# 04_Fan_Control.net
KiCad netlist of a schematic drawn in Altium Designer
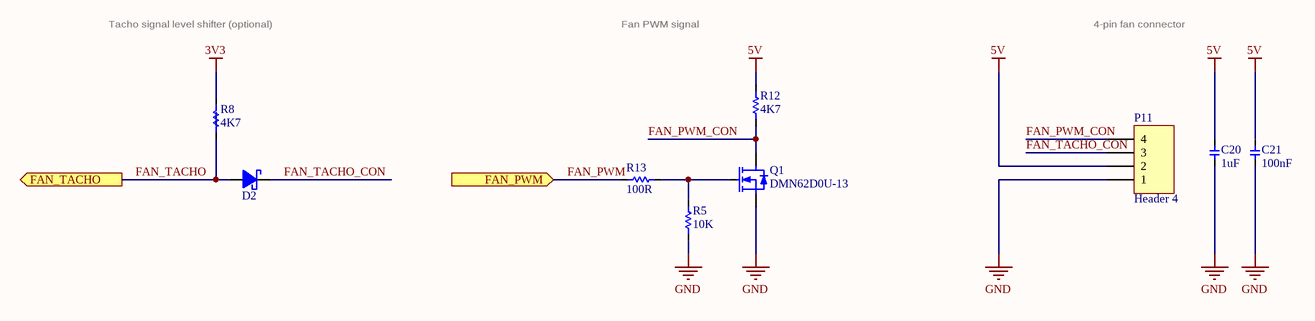
[diagram p0: 04_Fan_Control.SchDoc]

(export (version "E")
  (design (tool "Eeschema 10.0.6"))
  (components
    (comp (ref "C20")
      (value "1uF")
      (footprint "Moji Footprintovi:0603 - CAP HS")
      (description "Capacitor")
      (fields
        (field (name "MANUFACTURER") "Samsung Electro-Mechanics")
        (field (name "MANUFACTURER PART NUMBER") "CL10A105KB8NNNC")
      )
      (libsource (lib "Moji Schematici (1)") (part "Cap"))
    )
    (comp (ref "C21")
      (value "100nF")
      (footprint "Moji Footprintovi:0603 - CAP HS")
      (description "Capacitor")
      (fields
        (field (name "MANUFACTURER") "Samsung Electro-Mechanics")
        (field (name "MANUFACTURER PART NUMBER") "CL10B103KB8NNNC")
      )
      (libsource (lib "Moji Schematici (1)") (part "Cap"))
    )
    (comp (ref "D2")
      (value "Diode Schotky")
      (footprint "Moji Footprintovi:SOD123F")
      (fields
        (field (name "MANUFACTURER") "Nexperia USA Inc.")
        (field (name "MANUFACTURER PART NUMBER") "PMEG6010CEH,115")
        (field (name "DISTRIBUTOR PART NUMBER") "1727-3848-1-ND")
      )
      (libsource (lib "Moji Schematici (1)") (part "Diode Schotky"))
    )
    (comp (ref "P11")
      (value "Header 4")
      (footprint "Moji Footprintovi:Header 4x1")
      (description "Header, 4-Pin")
      (libsource (lib "Schematic_Misc") (part "Header 4"))
    )
    (comp (ref "Q1")
      (value "DMN62D0U-13")
      (footprint "Moji Footprintovi:SOT90P240X100-3N")
      (description "MOSFET N-CH 60V 0.38A")
      (fields
        (field (name "MANUFACTURER") "Diodes Incorporated")
        (field (name "DISTRIBUTOR PART NUMBER") "DMN62D0U-13DICT-ND")
      )
      (libsource (lib "Moji Schematici (1)") (part "DMN62D0U-13"))
    )
    (comp (ref "R5")
      (value "10K")
      (footprint "Footprint_Misc:0603 - HS")
      (description "Resistor")
      (fields
        (field (name "DISTRIBUTOR PART NUMBER") "RMCF0603JT10K0CT-ND")
        (field (name "MANUFACTURER") "Stackpole Electronics Inc")
      )
      (libsource (lib "Moji Schematici (1)") (part "Res"))
    )
    (comp (ref "R8")
      (value "4K7")
      (footprint "Footprint_Misc:0603 - HS")
      (description "Resistor")
      (fields
        (field (name "DISTRIBUTOR PART NUMBER") "RMCF0603FT4K70CT-ND")
        (field (name "MANUFACTURER") "Stackpole Electronics Inc")
      )
      (libsource (lib "Moji Schematici (1)") (part "Res"))
    )
    (comp (ref "R12")
      (value "4K7")
      (footprint "Footprint_Misc:0603 - HS")
      (description "Resistor")
      (fields
        (field (name "DISTRIBUTOR PART NUMBER") "RMCF0603FT4K70CT-ND")
        (field (name "MANUFACTURER") "Stackpole Electronics Inc")
      )
      (libsource (lib "Moji Schematici (1)") (part "Res"))
    )
    (comp (ref "R13")
      (value "100R")
      (footprint "Footprint_Misc:0603 - HS")
      (description "Resistor")
      (fields
        (field (name "DISTRIBUTOR PART NUMBER") "RMCF0603FT100RCT-ND")
        (field (name "MANUFACTURER") "Stackpole Electronics Inc")
      )
      (libsource (lib "Moji Schematici (1)") (part "Res"))
    )
  )
  (nets
    (net (code "1") (name "/FAN_PWM") (class "Default")
      (node (ref "R13") (pin "2") (pinfunction "2_2") (pintype "passive"))
    )
    (net (code "2") (name "/FAN_PWM_CON") (class "Default")
      (node (ref "P11") (pin "4") (pinfunction "4_4") (pintype "passive"))
      (node (ref "Q1") (pin "3") (pinfunction "D_3") (pintype "passive"))
      (node (ref "R12") (pin "1") (pinfunction "1_1") (pintype "passive"))
    )
    (net (code "3") (name "/FAN_TACHO") (class "Default")
      (node (ref "D2") (pin "A") (pinfunction "A_A") (pintype "passive"))
      (node (ref "R8") (pin "1") (pinfunction "1_1") (pintype "passive"))
    )
    (net (code "4") (name "/FAN_TACHO_CON") (class "Default")
      (node (ref "D2") (pin "K") (pinfunction "K_K") (pintype "passive"))
      (node (ref "P11") (pin "3") (pinfunction "3_3") (pintype "passive"))
    )
    (net (code "5") (name "3V3") (class "Default")
      (node (ref "R8") (pin "2") (pinfunction "2_2") (pintype "passive"))
    )
    (net (code "6") (name "5V") (class "Default")
      (node (ref "C20") (pin "1") (pinfunction "1_1") (pintype "passive"))
      (node (ref "C21") (pin "1") (pinfunction "1_1") (pintype "passive"))
      (node (ref "P11") (pin "2") (pinfunction "2_2") (pintype "passive"))
      (node (ref "R12") (pin "2") (pinfunction "2_2") (pintype "passive"))
    )
    (net (code "7") (name "GND") (class "Default")
      (node (ref "C20") (pin "2") (pinfunction "2_2") (pintype "passive"))
      (node (ref "C21") (pin "2") (pinfunction "2_2") (pintype "passive"))
      (node (ref "P11") (pin "1") (pinfunction "1_1") (pintype "passive"))
      (node (ref "Q1") (pin "2") (pinfunction "S_2") (pintype "passive"))
      (node (ref "R5") (pin "2") (pinfunction "2_2") (pintype "passive"))
    )
    (net (code "8") (name "Net-(Q1-G)") (class "Default")
      (node (ref "Q1") (pin "1") (pinfunction "G_1") (pintype "passive"))
      (node (ref "R13") (pin "1") (pinfunction "1_1") (pintype "passive"))
      (node (ref "R5") (pin "1") (pinfunction "1_1") (pintype "passive"))
    )
  )
)
